# ESP32.net
KiCad netlist of a schematic drawn in Altium Designer
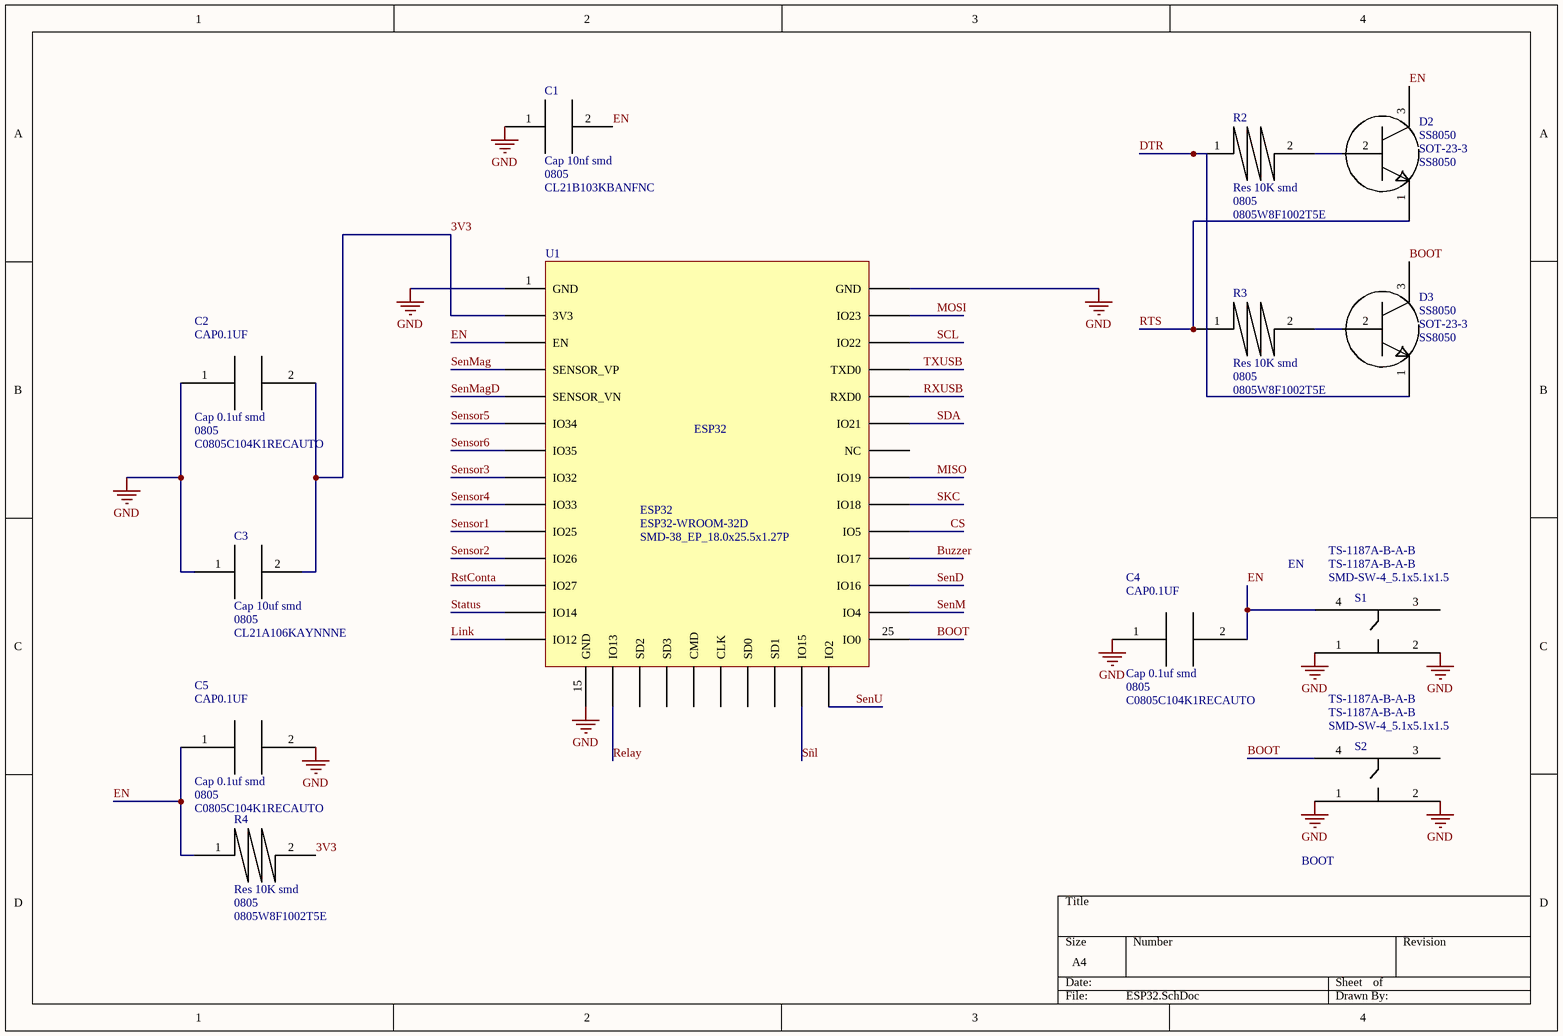
[diagram p0: ESP32.SchDoc]

(export (version "E")
  (design (tool "Eeschema 10.0.6"))
  (components
    (comp (ref "C1")
      (value "Cap 10nf smd")
      (footprint "CAP10NFSMD")
      (description "10nf")
      (fields (field (name "PACKAGE") "0805") (field (name "MFR.PART #") "CL21B103KBANFNC"))
      (libsource (lib "Integrated_Library") (part "Cap 10nf smd"))
    )
    (comp (ref "C2")
      (value "Cap 0.1uf smd")
      (footprint "CAP0.1UFSMD")
      (description "0.1uf")
      (fields (field (name "PACKAGE") "0805") (field (name "MFR.PART #") "C0805C104K1RECAUTO"))
      (libsource (lib "Integrated_Library") (part "Cap 0.1uf smd"))
    )
    (comp (ref "C3")
      (value "Cap 10uf smd")
      (footprint "CAP10UFSMD")
      (description "10uf")
      (fields (field (name "PACKAGE") "0805") (field (name "MFR.PART #") "CL21A106KAYNNNE"))
      (libsource (lib "Integrated_Library") (part "Cap 10uf smd"))
    )
    (comp (ref "C4")
      (value "Cap 0.1uf smd")
      (footprint "CAP0.1UFSMD")
      (description "0.1uf")
      (fields (field (name "PACKAGE") "0805") (field (name "MFR.PART #") "C0805C104K1RECAUTO"))
      (libsource (lib "Integrated_Library") (part "Cap 0.1uf smd"))
    )
    (comp (ref "C5")
      (value "Cap 0.1uf smd")
      (footprint "CAP0.1UFSMD")
      (description "0.1uf")
      (fields (field (name "PACKAGE") "0805") (field (name "MFR.PART #") "C0805C104K1RECAUTO"))
      (libsource (lib "Integrated_Library") (part "Cap 0.1uf smd"))
    )
    (comp (ref "D2")
      (value "SS8050")
      (footprint "SS8050")
      (fields (field (name "PACKAGE") "SOT-23-3") (field (name "MFR.PART #") "SS8050"))
      (libsource (lib "Integrated_Library") (part "SS8050"))
    )
    (comp (ref "D3")
      (value "SS8050")
      (footprint "SS8050")
      (fields (field (name "PACKAGE") "SOT-23-3") (field (name "MFR.PART #") "SS8050"))
      (libsource (lib "Integrated_Library") (part "SS8050"))
    )
    (comp (ref "R2")
      (value "Res 10K smd")
      (footprint "RES 10K")
      (description "10K")
      (fields (field (name "PACKAGE") "0805") (field (name "MFR.PART #") "0805W8F1002T5E"))
      (libsource (lib "Integrated_Library") (part "Res 10K smd"))
    )
    (comp (ref "R3")
      (value "Res 10K smd")
      (footprint "RES 10K")
      (description "10K")
      (fields (field (name "PACKAGE") "0805") (field (name "MFR.PART #") "0805W8F1002T5E"))
      (libsource (lib "Integrated_Library") (part "Res 10K smd"))
    )
    (comp (ref "R4")
      (value "Res 10K smd")
      (footprint "RES 10K")
      (description "10K")
      (fields (field (name "PACKAGE") "0805") (field (name "MFR.PART #") "0805W8F1002T5E"))
      (libsource (lib "Integrated_Library") (part "Res 10K smd"))
    )
    (comp (ref "S1")
      (value "TS-1187A-B-A-B")
      (footprint "TS-1187A-B-A-B")
      (fields (field (name "MFR.PART #") "TS-1187A-B-A-B") (field (name "PACKAGE") "SMD-SW-4_5.1x5.1x1.5"))
      (libsource (lib "Integrated_Library") (part "TS-1187A-B-A-B"))
    )
    (comp (ref "S2")
      (value "TS-1187A-B-A-B")
      (footprint "TS-1187A-B-A-B")
      (fields (field (name "MFR.PART #") "TS-1187A-B-A-B") (field (name "PACKAGE") "SMD-SW-4_5.1x5.1x1.5"))
      (libsource (lib "Integrated_Library") (part "TS-1187A-B-A-B"))
    )
    (comp (ref "U1")
      (value "ESP32")
      (footprint "ESP32")
      (fields
        (field (name "PACKAGE") "SMD-38_EP_18.0x25.5x1.27P")
        (field (name "MFR.PART #") "ESP32-WROOM-32D")
      )
      (libsource (lib "Integrated_Library") (part "ESP32"))
    )
  )
  (nets
    (net (code "1") (name "/3V3") (class "Default")
      (node (ref "C2") (pin "2") (pinfunction "2_2") (pintype "passive"))
      (node (ref "C3") (pin "2") (pinfunction "2_2") (pintype "passive"))
      (node (ref "R4") (pin "2") (pinfunction "2_2") (pintype "passive"))
      (node (ref "U1") (pin "2") (pinfunction "3V3_2") (pintype "passive"))
    )
    (net (code "2") (name "/BOOT") (class "Default")
      (node (ref "D3") (pin "3") (pinfunction "3_3") (pintype "passive"))
      (node (ref "S2") (pin "4") (pinfunction "4_4") (pintype "passive"))
      (node (ref "U1") (pin "25") (pinfunction "IO0_25") (pintype "passive"))
    )
    (net (code "3") (name "/Buzzer") (class "Default")
      (node (ref "U1") (pin "28") (pinfunction "IO17_28") (pintype "passive"))
    )
    (net (code "4") (name "/CS") (class "Default")
      (node (ref "U1") (pin "29") (pinfunction "IO5_29") (pintype "passive"))
    )
    (net (code "5") (name "/DTR") (class "Default")
      (node (ref "D3") (pin "1") (pinfunction "1_1") (pintype "passive"))
      (node (ref "R2") (pin "1") (pinfunction "1_1") (pintype "passive"))
    )
    (net (code "6") (name "/EN") (class "Default")
      (node (ref "C1") (pin "2") (pinfunction "2_2") (pintype "passive"))
      (node (ref "C4") (pin "2") (pinfunction "2_2") (pintype "passive"))
      (node (ref "C5") (pin "1") (pinfunction "1_1") (pintype "passive"))
      (node (ref "D2") (pin "3") (pinfunction "3_3") (pintype "passive"))
      (node (ref "R4") (pin "1") (pinfunction "1_1") (pintype "passive"))
      (node (ref "S1") (pin "4") (pinfunction "4_4") (pintype "passive"))
      (node (ref "U1") (pin "3") (pinfunction "EN_3") (pintype "passive"))
    )
    (net (code "7") (name "/Link") (class "Default")
      (node (ref "U1") (pin "14") (pinfunction "IO12_14") (pintype "passive"))
    )
    (net (code "8") (name "/MISO") (class "Default")
      (node (ref "U1") (pin "31") (pinfunction "IO19_31") (pintype "passive"))
    )
    (net (code "9") (name "/MOSI") (class "Default")
      (node (ref "U1") (pin "37") (pinfunction "IO23_37") (pintype "passive"))
    )
    (net (code "10") (name "/RTS") (class "Default")
      (node (ref "D2") (pin "1") (pinfunction "1_1") (pintype "passive"))
      (node (ref "R3") (pin "1") (pinfunction "1_1") (pintype "passive"))
    )
    (net (code "11") (name "/RXUSB") (class "Default")
      (node (ref "U1") (pin "34") (pinfunction "RXD0_34") (pintype "passive"))
    )
    (net (code "12") (name "/Relay") (class "Default")
      (node (ref "U1") (pin "16") (pinfunction "IO13_16") (pintype "passive"))
    )
    (net (code "13") (name "/RstConta") (class "Default")
      (node (ref "U1") (pin "12") (pinfunction "IO27_12") (pintype "passive"))
    )
    (net (code "14") (name "/SCL") (class "Default")
      (node (ref "U1") (pin "36") (pinfunction "IO22_36") (pintype "passive"))
    )
    (net (code "15") (name "/SDA") (class "Default")
      (node (ref "U1") (pin "33") (pinfunction "IO21_33") (pintype "passive"))
    )
    (net (code "16") (name "/SKC") (class "Default")
      (node (ref "U1") (pin "30") (pinfunction "IO18_30") (pintype "passive"))
    )
    (net (code "17") (name "/SenD") (class "Default")
      (node (ref "U1") (pin "27") (pinfunction "IO16_27") (pintype "passive"))
    )
    (net (code "18") (name "/SenM") (class "Default")
      (node (ref "U1") (pin "26") (pinfunction "IO4_26") (pintype "passive"))
    )
    (net (code "19") (name "/SenMag") (class "Default")
      (node (ref "U1") (pin "4") (pinfunction "SENSOR_VP_4") (pintype "passive"))
    )
    (net (code "20") (name "/SenMagD") (class "Default")
      (node (ref "U1") (pin "5") (pinfunction "SENSOR_VN_5") (pintype "passive"))
    )
    (net (code "21") (name "/SenU") (class "Default")
      (node (ref "U1") (pin "24") (pinfunction "IO2_24") (pintype "passive"))
    )
    (net (code "22") (name "/Sensor1") (class "Default")
      (node (ref "U1") (pin "10") (pinfunction "IO25_10") (pintype "passive"))
    )
    (net (code "23") (name "/Sensor2") (class "Default")
      (node (ref "U1") (pin "11") (pinfunction "IO26_11") (pintype "passive"))
    )
    (net (code "24") (name "/Sensor3") (class "Default")
      (node (ref "U1") (pin "8") (pinfunction "IO32_8") (pintype "passive"))
    )
    (net (code "25") (name "/Sensor4") (class "Default")
      (node (ref "U1") (pin "9") (pinfunction "IO33_9") (pintype "passive"))
    )
    (net (code "26") (name "/Sensor5") (class "Default")
      (node (ref "U1") (pin "6") (pinfunction "IO34_6") (pintype "passive"))
    )
    (net (code "27") (name "/Sensor6") (class "Default")
      (node (ref "U1") (pin "7") (pinfunction "IO35_7") (pintype "passive"))
    )
    (net (code "28") (name "/Status") (class "Default")
      (node (ref "U1") (pin "13") (pinfunction "IO14_13") (pintype "passive"))
    )
    (net (code "29") (name "/Sñl") (class "Default")
      (node (ref "U1") (pin "23") (pinfunction "IO15_23") (pintype "passive"))
    )
    (net (code "30") (name "/TXUSB") (class "Default")
      (node (ref "U1") (pin "35") (pinfunction "TXD0_35") (pintype "passive"))
    )
    (net (code "31") (name "GND") (class "Default")
      (node (ref "C1") (pin "1") (pinfunction "1_1") (pintype "passive"))
      (node (ref "C2") (pin "1") (pinfunction "1_1") (pintype "passive"))
      (node (ref "C3") (pin "1") (pinfunction "1_1") (pintype "passive"))
      (node (ref "C4") (pin "1") (pinfunction "1_1") (pintype "passive"))
      (node (ref "C5") (pin "2") (pinfunction "2_2") (pintype "passive"))
      (node (ref "S1") (pin "1") (pinfunction "1_1") (pintype "passive"))
      (node (ref "S1") (pin "2") (pinfunction "2_2") (pintype "passive"))
      (node (ref "S2") (pin "1") (pinfunction "1_1") (pintype "passive"))
      (node (ref "S2") (pin "2") (pinfunction "2_2") (pintype "passive"))
      (node (ref "U1") (pin "1") (pinfunction "GND_1") (pintype "passive"))
      (node (ref "U1") (pin "15") (pinfunction "GND_15") (pintype "passive"))
      (node (ref "U1") (pin "38") (pinfunction "GND_38") (pintype "passive"))
    )
    (net (code "32") (name "Net-(D2-Pad2)") (class "Default")
      (node (ref "D2") (pin "2") (pinfunction "2_2") (pintype "passive"))
      (node (ref "R2") (pin "2") (pinfunction "2_2") (pintype "passive"))
    )
    (net (code "33") (name "Net-(D3-Pad2)") (class "Default")
      (node (ref "D3") (pin "2") (pinfunction "2_2") (pintype "passive"))
      (node (ref "R3") (pin "2") (pinfunction "2_2") (pintype "passive"))
    )
    (net (code "34") (name "unconnected-(S1-Pad3)") (class "Default")
      (node (ref "S1") (pin "3") (pinfunction "3_3") (pintype "passive"))
    )
    (net (code "35") (name "unconnected-(S2-Pad3)") (class "Default")
      (node (ref "S2") (pin "3") (pinfunction "3_3") (pintype "passive"))
    )
    (net (code "36") (name "unconnected-(U1-CLK-Pad20)") (class "Default")
      (node (ref "U1") (pin "20") (pinfunction "CLK_20") (pintype "passive"))
    )
    (net (code "37") (name "unconnected-(U1-CMD-Pad19)") (class "Default")
      (node (ref "U1") (pin "19") (pinfunction "CMD_19") (pintype "passive"))
    )
    (net (code "38") (name "unconnected-(U1-NC-Pad32)") (class "Default")
      (node (ref "U1") (pin "32") (pinfunction "NC_32") (pintype "passive"))
    )
    (net (code "39") (name "unconnected-(U1-SD0-Pad21)") (class "Default")
      (node (ref "U1") (pin "21") (pinfunction "SD0_21") (pintype "passive"))
    )
    (net (code "40") (name "unconnected-(U1-SD1-Pad22)") (class "Default")
      (node (ref "U1") (pin "22") (pinfunction "SD1_22") (pintype "passive"))
    )
    (net (code "41") (name "unconnected-(U1-SD2-Pad17)") (class "Default")
      (node (ref "U1") (pin "17") (pinfunction "SD2_17") (pintype "passive"))
    )
    (net (code "42") (name "unconnected-(U1-SD3-Pad18)") (class "Default")
      (node (ref "U1") (pin "18") (pinfunction "SD3_18") (pintype "passive"))
    )
  )
)
